# yaesulink.net
KiCad netlist of a schematic drawn in EAGLE
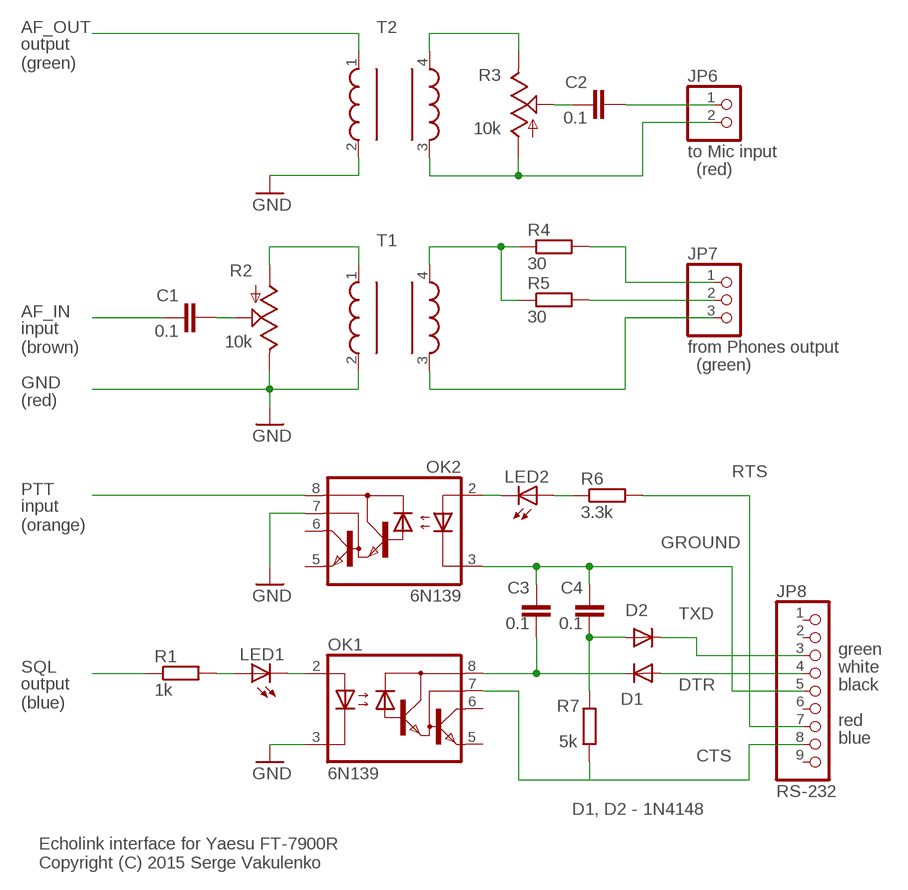
[diagram p0: schematic, sheet 1]

(export (version "E")
  (design (tool "Eeschema 10.0.6"))
  (components
    (comp (ref "C1")
      (value "0.1")
      (footprint "eagle-import:C025-024X044")
      (libsource (lib "eagle-import") (part "C-EU025-024X044"))
    )
    (comp (ref "C2")
      (value "0.1")
      (footprint "eagle-import:C025-024X044")
      (libsource (lib "eagle-import") (part "C-EU025-024X044"))
    )
    (comp (ref "C3")
      (value "0.1")
      (footprint "eagle-import:C025-024X044")
      (libsource (lib "eagle-import") (part "C-EU025-024X044"))
    )
    (comp (ref "C4")
      (value "0.1")
      (footprint "eagle-import:C025-024X044")
      (libsource (lib "eagle-import") (part "C-EU025-024X044"))
    )
    (comp (ref "D1")
      (value "1N4148DO35-7")
      (footprint "eagle-import:DO35-7")
      (libsource (lib "eagle-import") (part "1N4148DO35-7"))
    )
    (comp (ref "D2")
      (value "1N4148DO35-7")
      (footprint "eagle-import:DO35-7")
      (libsource (lib "eagle-import") (part "1N4148DO35-7"))
    )
    (comp (ref "JP6")
      (value "to Mic input")
      (footprint "eagle-import:1X02")
      (libsource (lib "eagle-import") (part "PINHD-1X2"))
    )
    (comp (ref "JP7")
      (value "from Phones output")
      (footprint "eagle-import:1X03")
      (libsource (lib "eagle-import") (part "PINHD-1X3"))
    )
    (comp (ref "JP8")
      (value "RS-232")
      (footprint "eagle-import:1X09")
      (libsource (lib "eagle-import") (part "PINHD-1X9"))
    )
    (comp (ref "LED1")
      (value "LED3MM")
      (footprint "eagle-import:LED3MM")
      (libsource (lib "eagle-import") (part "LED3MM"))
    )
    (comp (ref "LED2")
      (value "LED3MM")
      (footprint "eagle-import:LED3MM")
      (libsource (lib "eagle-import") (part "LED3MM"))
    )
    (comp (ref "OK1")
      (value "6N139")
      (footprint "eagle-import:DIL08")
      (fields
        (field (name "MF") "VISHAY/TELEFUNKEN")
        (field (name "MPN") "6N138")
        (field (name "MPN_1") "6N139")
      )
      (libsource (lib "eagle-import") (part "6N138"))
    )
    (comp (ref "OK2")
      (value "6N139")
      (footprint "eagle-import:DIL08")
      (fields
        (field (name "MF") "VISHAY/TELEFUNKEN")
        (field (name "MPN") "6N138")
        (field (name "MPN_1") "6N139")
      )
      (libsource (lib "eagle-import") (part "6N138"))
    )
    (comp (ref "R1")
      (value "1k")
      (footprint "eagle-import:0207_10")
      (libsource (lib "eagle-import") (part "R-EU_0207/10"))
    )
    (comp (ref "R2")
      (value "10k")
      (footprint "eagle-import:B25P")
      (libsource (lib "eagle-import") (part "TRIM_US-B25P"))
    )
    (comp (ref "R3")
      (value "10k")
      (footprint "eagle-import:B25P")
      (libsource (lib "eagle-import") (part "TRIM_US-B25P"))
    )
    (comp (ref "R4")
      (value "30")
      (footprint "eagle-import:0207_10")
      (libsource (lib "eagle-import") (part "R-EU_0207/10"))
    )
    (comp (ref "R5")
      (value "30")
      (footprint "eagle-import:0207_10")
      (libsource (lib "eagle-import") (part "R-EU_0207/10"))
    )
    (comp (ref "R6")
      (value "3.3k")
      (footprint "eagle-import:0207_10")
      (libsource (lib "eagle-import") (part "R-EU_0207/10"))
    )
    (comp (ref "R7")
      (value "5k")
      (footprint "eagle-import:0207_10")
      (libsource (lib "eagle-import") (part "R-EU_0207/10"))
    )
    (comp (ref "T1")
      (value "TRANSFORMERPTH")
      (footprint "eagle-import:TRANSFORMER")
      (libsource (lib "eagle-import") (part "TRANSFORMERPTH"))
    )
    (comp (ref "T2")
      (value "TRANSFORMERPTH")
      (footprint "eagle-import:TRANSFORMER")
      (libsource (lib "eagle-import") (part "TRANSFORMERPTH"))
    )
  )
  (nets
    (net (code "1") (name "/AF_IN") (class "Default")
      (node (ref "C1") (pin "1") (pinfunction "1_1") (pintype "passive"))
    )
    (net (code "2") (name "/AF_OUT") (class "Default")
      (node (ref "T2") (pin "1") (pinfunction "1_1") (pintype "bidirectional"))
    )
    (net (code "3") (name "/CTS") (class "Default")
      (node (ref "JP8") (pin "8") (pinfunction "8_8") (pintype "passive"))
      (node (ref "OK1") (pin "7") (pinfunction "VB_7") (pintype "passive"))
      (node (ref "R7") (pin "1") (pinfunction "1_1") (pintype "passive"))
    )
    (net (code "4") (name "/DTR") (class "Default")
      (node (ref "D1") (pin "A") (pinfunction "A_A") (pintype "passive"))
      (node (ref "JP8") (pin "4") (pinfunction "4_4") (pintype "passive"))
    )
    (net (code "5") (name "/GROUND") (class "Default")
      (node (ref "C3") (pin "1") (pinfunction "1_1") (pintype "passive"))
      (node (ref "C4") (pin "1") (pinfunction "1_1") (pintype "passive"))
      (node (ref "JP8") (pin "5") (pinfunction "5_5") (pintype "passive"))
      (node (ref "OK2") (pin "3") (pinfunction "C_3") (pintype "passive"))
    )
    (net (code "6") (name "/PTT") (class "Default")
      (node (ref "OK2") (pin "8") (pinfunction "VCC_8") (pintype "passive"))
    )
    (net (code "7") (name "/RTS") (class "Default")
      (node (ref "JP8") (pin "7") (pinfunction "7_7") (pintype "passive"))
      (node (ref "R6") (pin "2") (pinfunction "2_2") (pintype "passive"))
    )
    (net (code "8") (name "/SQL") (class "Default")
      (node (ref "R1") (pin "1") (pinfunction "1_1") (pintype "passive"))
    )
    (net (code "9") (name "/TXD") (class "Default")
      (node (ref "D2") (pin "C") (pinfunction "C_C") (pintype "passive"))
      (node (ref "JP8") (pin "3") (pinfunction "3_3") (pintype "passive"))
    )
    (net (code "10") (name "GND") (class "Default")
      (node (ref "OK1") (pin "3") (pinfunction "C_3") (pintype "passive"))
      (node (ref "OK2") (pin "7") (pinfunction "VB_7") (pintype "passive"))
      (node (ref "R2") (pin "E") (pinfunction "E_E") (pintype "passive"))
      (node (ref "T1") (pin "2") (pinfunction "2_2") (pintype "bidirectional"))
      (node (ref "T2") (pin "2") (pinfunction "2_2") (pintype "bidirectional"))
    )
    (net (code "11") (name "Net-(C1-Pad2)") (class "Default")
      (node (ref "C1") (pin "2") (pinfunction "2_2") (pintype "passive"))
      (node (ref "R2") (pin "S") (pinfunction "S_S") (pintype "passive"))
    )
    (net (code "12") (name "Net-(C2-Pad1)") (class "Default")
      (node (ref "C2") (pin "1") (pinfunction "1_1") (pintype "passive"))
      (node (ref "R3") (pin "S") (pinfunction "S_S") (pintype "passive"))
    )
    (net (code "13") (name "Net-(C2-Pad2)") (class "Default")
      (node (ref "C2") (pin "2") (pinfunction "2_2") (pintype "passive"))
      (node (ref "JP6") (pin "1") (pinfunction "1_1") (pintype "passive"))
    )
    (net (code "14") (name "Net-(C4-Pad2)") (class "Default")
      (node (ref "C4") (pin "2") (pinfunction "2_2") (pintype "passive"))
      (node (ref "D2") (pin "A") (pinfunction "A_A") (pintype "passive"))
      (node (ref "R7") (pin "2") (pinfunction "2_2") (pintype "passive"))
    )
    (net (code "15") (name "Net-(JP6-Pad2)") (class "Default")
      (node (ref "JP6") (pin "2") (pinfunction "2_2") (pintype "passive"))
      (node (ref "R3") (pin "A") (pinfunction "A_A") (pintype "passive"))
      (node (ref "T2") (pin "3") (pinfunction "3_3") (pintype "bidirectional"))
    )
    (net (code "16") (name "Net-(JP7-Pad1)") (class "Default")
      (node (ref "JP7") (pin "1") (pinfunction "1_1") (pintype "passive"))
      (node (ref "R4") (pin "2") (pinfunction "2_2") (pintype "passive"))
    )
    (net (code "17") (name "Net-(JP7-Pad2)") (class "Default")
      (node (ref "JP7") (pin "2") (pinfunction "2_2") (pintype "passive"))
      (node (ref "R5") (pin "2") (pinfunction "2_2") (pintype "passive"))
    )
    (net (code "18") (name "Net-(JP7-Pad3)") (class "Default")
      (node (ref "JP7") (pin "3") (pinfunction "3_3") (pintype "passive"))
      (node (ref "T1") (pin "3") (pinfunction "3_3") (pintype "bidirectional"))
    )
    (net (code "19") (name "Net-(LED1-C)") (class "Default")
      (node (ref "LED1") (pin "K") (pinfunction "C_K") (pintype "passive"))
      (node (ref "OK1") (pin "2") (pinfunction "A_2") (pintype "passive"))
    )
    (net (code "20") (name "Net-(LED1-PadA)") (class "Default")
      (node (ref "LED1") (pin "A") (pinfunction "A_A") (pintype "passive"))
      (node (ref "R1") (pin "2") (pinfunction "2_2") (pintype "passive"))
    )
    (net (code "21") (name "Net-(LED2-C)") (class "Default")
      (node (ref "LED2") (pin "K") (pinfunction "C_K") (pintype "passive"))
      (node (ref "OK2") (pin "2") (pinfunction "A_2") (pintype "passive"))
    )
    (net (code "22") (name "Net-(LED2-PadA)") (class "Default")
      (node (ref "LED2") (pin "A") (pinfunction "A_A") (pintype "passive"))
      (node (ref "R6") (pin "1") (pinfunction "1_1") (pintype "passive"))
    )
    (net (code "23") (name "Net-(OK1-VCC)") (class "Default")
      (node (ref "C3") (pin "2") (pinfunction "2_2") (pintype "passive"))
      (node (ref "D1") (pin "C") (pinfunction "C_C") (pintype "passive"))
      (node (ref "OK1") (pin "8") (pinfunction "VCC_8") (pintype "passive"))
    )
    (net (code "24") (name "Net-(R2-PadA)") (class "Default")
      (node (ref "R2") (pin "A") (pinfunction "A_A") (pintype "passive"))
      (node (ref "T1") (pin "1") (pinfunction "1_1") (pintype "bidirectional"))
    )
    (net (code "25") (name "Net-(R3-PadE)") (class "Default")
      (node (ref "R3") (pin "E") (pinfunction "E_E") (pintype "passive"))
      (node (ref "T2") (pin "4") (pinfunction "4_4") (pintype "bidirectional"))
    )
    (net (code "26") (name "Net-(R4-Pad1)") (class "Default")
      (node (ref "R4") (pin "1") (pinfunction "1_1") (pintype "passive"))
      (node (ref "R5") (pin "1") (pinfunction "1_1") (pintype "passive"))
      (node (ref "T1") (pin "4") (pinfunction "4_4") (pintype "bidirectional"))
    )
    (net (code "27") (name "unconnected-(JP8-Pad1)") (class "Default")
      (node (ref "JP8") (pin "1") (pinfunction "1_1") (pintype "passive"))
    )
    (net (code "28") (name "unconnected-(JP8-Pad2)") (class "Default")
      (node (ref "JP8") (pin "2") (pinfunction "2_2") (pintype "passive"))
    )
    (net (code "29") (name "unconnected-(JP8-Pad6)") (class "Default")
      (node (ref "JP8") (pin "6") (pinfunction "6_6") (pintype "passive"))
    )
    (net (code "30") (name "unconnected-(JP8-Pad9)") (class "Default")
      (node (ref "JP8") (pin "9") (pinfunction "9_9") (pintype "passive"))
    )
    (net (code "31") (name "unconnected-(OK1-GND-Pad5)") (class "Default")
      (node (ref "OK1") (pin "5") (pinfunction "GND_5") (pintype "passive"))
    )
    (net (code "32") (name "unconnected-(OK1-VO-Pad6)") (class "Default")
      (node (ref "OK1") (pin "6") (pinfunction "VO_6") (pintype "passive"))
    )
    (net (code "33") (name "unconnected-(OK2-GND-Pad5)") (class "Default")
      (node (ref "OK2") (pin "5") (pinfunction "GND_5") (pintype "passive"))
    )
    (net (code "34") (name "unconnected-(OK2-VO-Pad6)") (class "Default")
      (node (ref "OK2") (pin "6") (pinfunction "VO_6") (pintype "passive"))
    )
  )
)
